# 549-anamdev-forceSensor.net
KiCad netlist of a schematic drawn in EAGLE
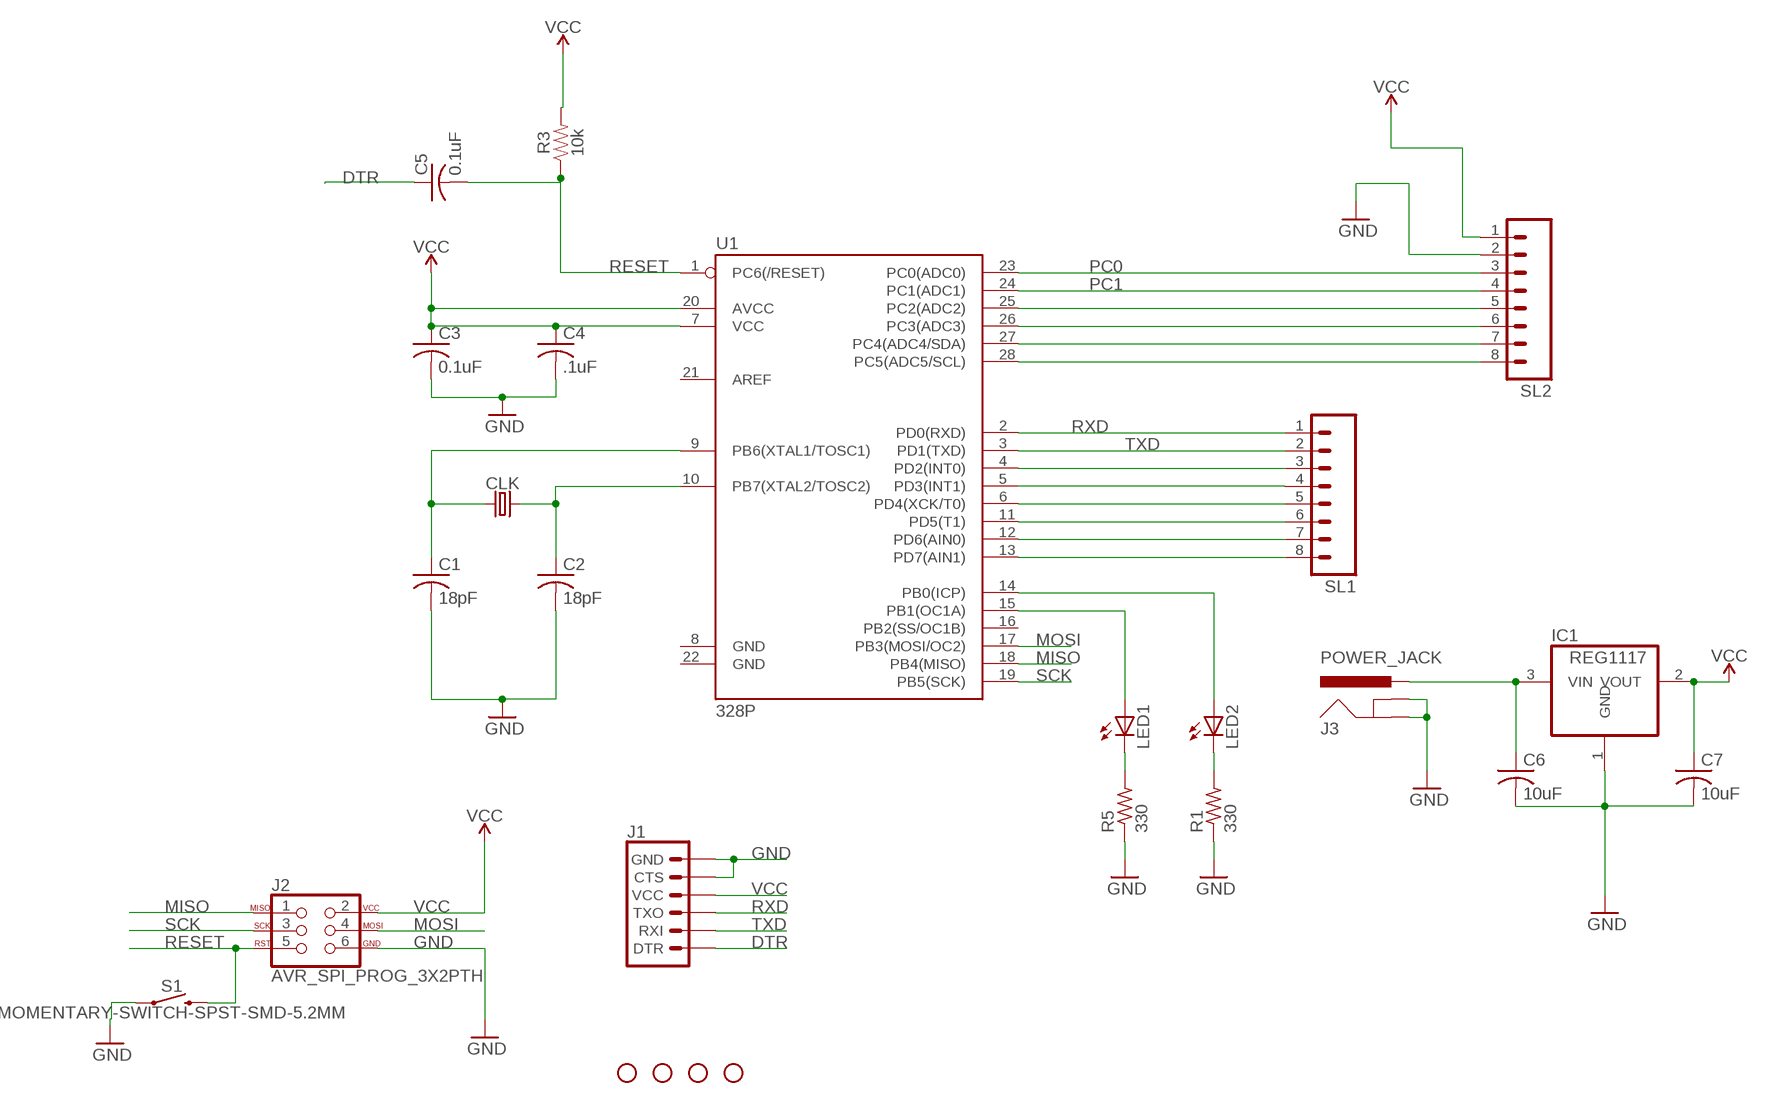
[diagram p0: schematic, sheet 1]
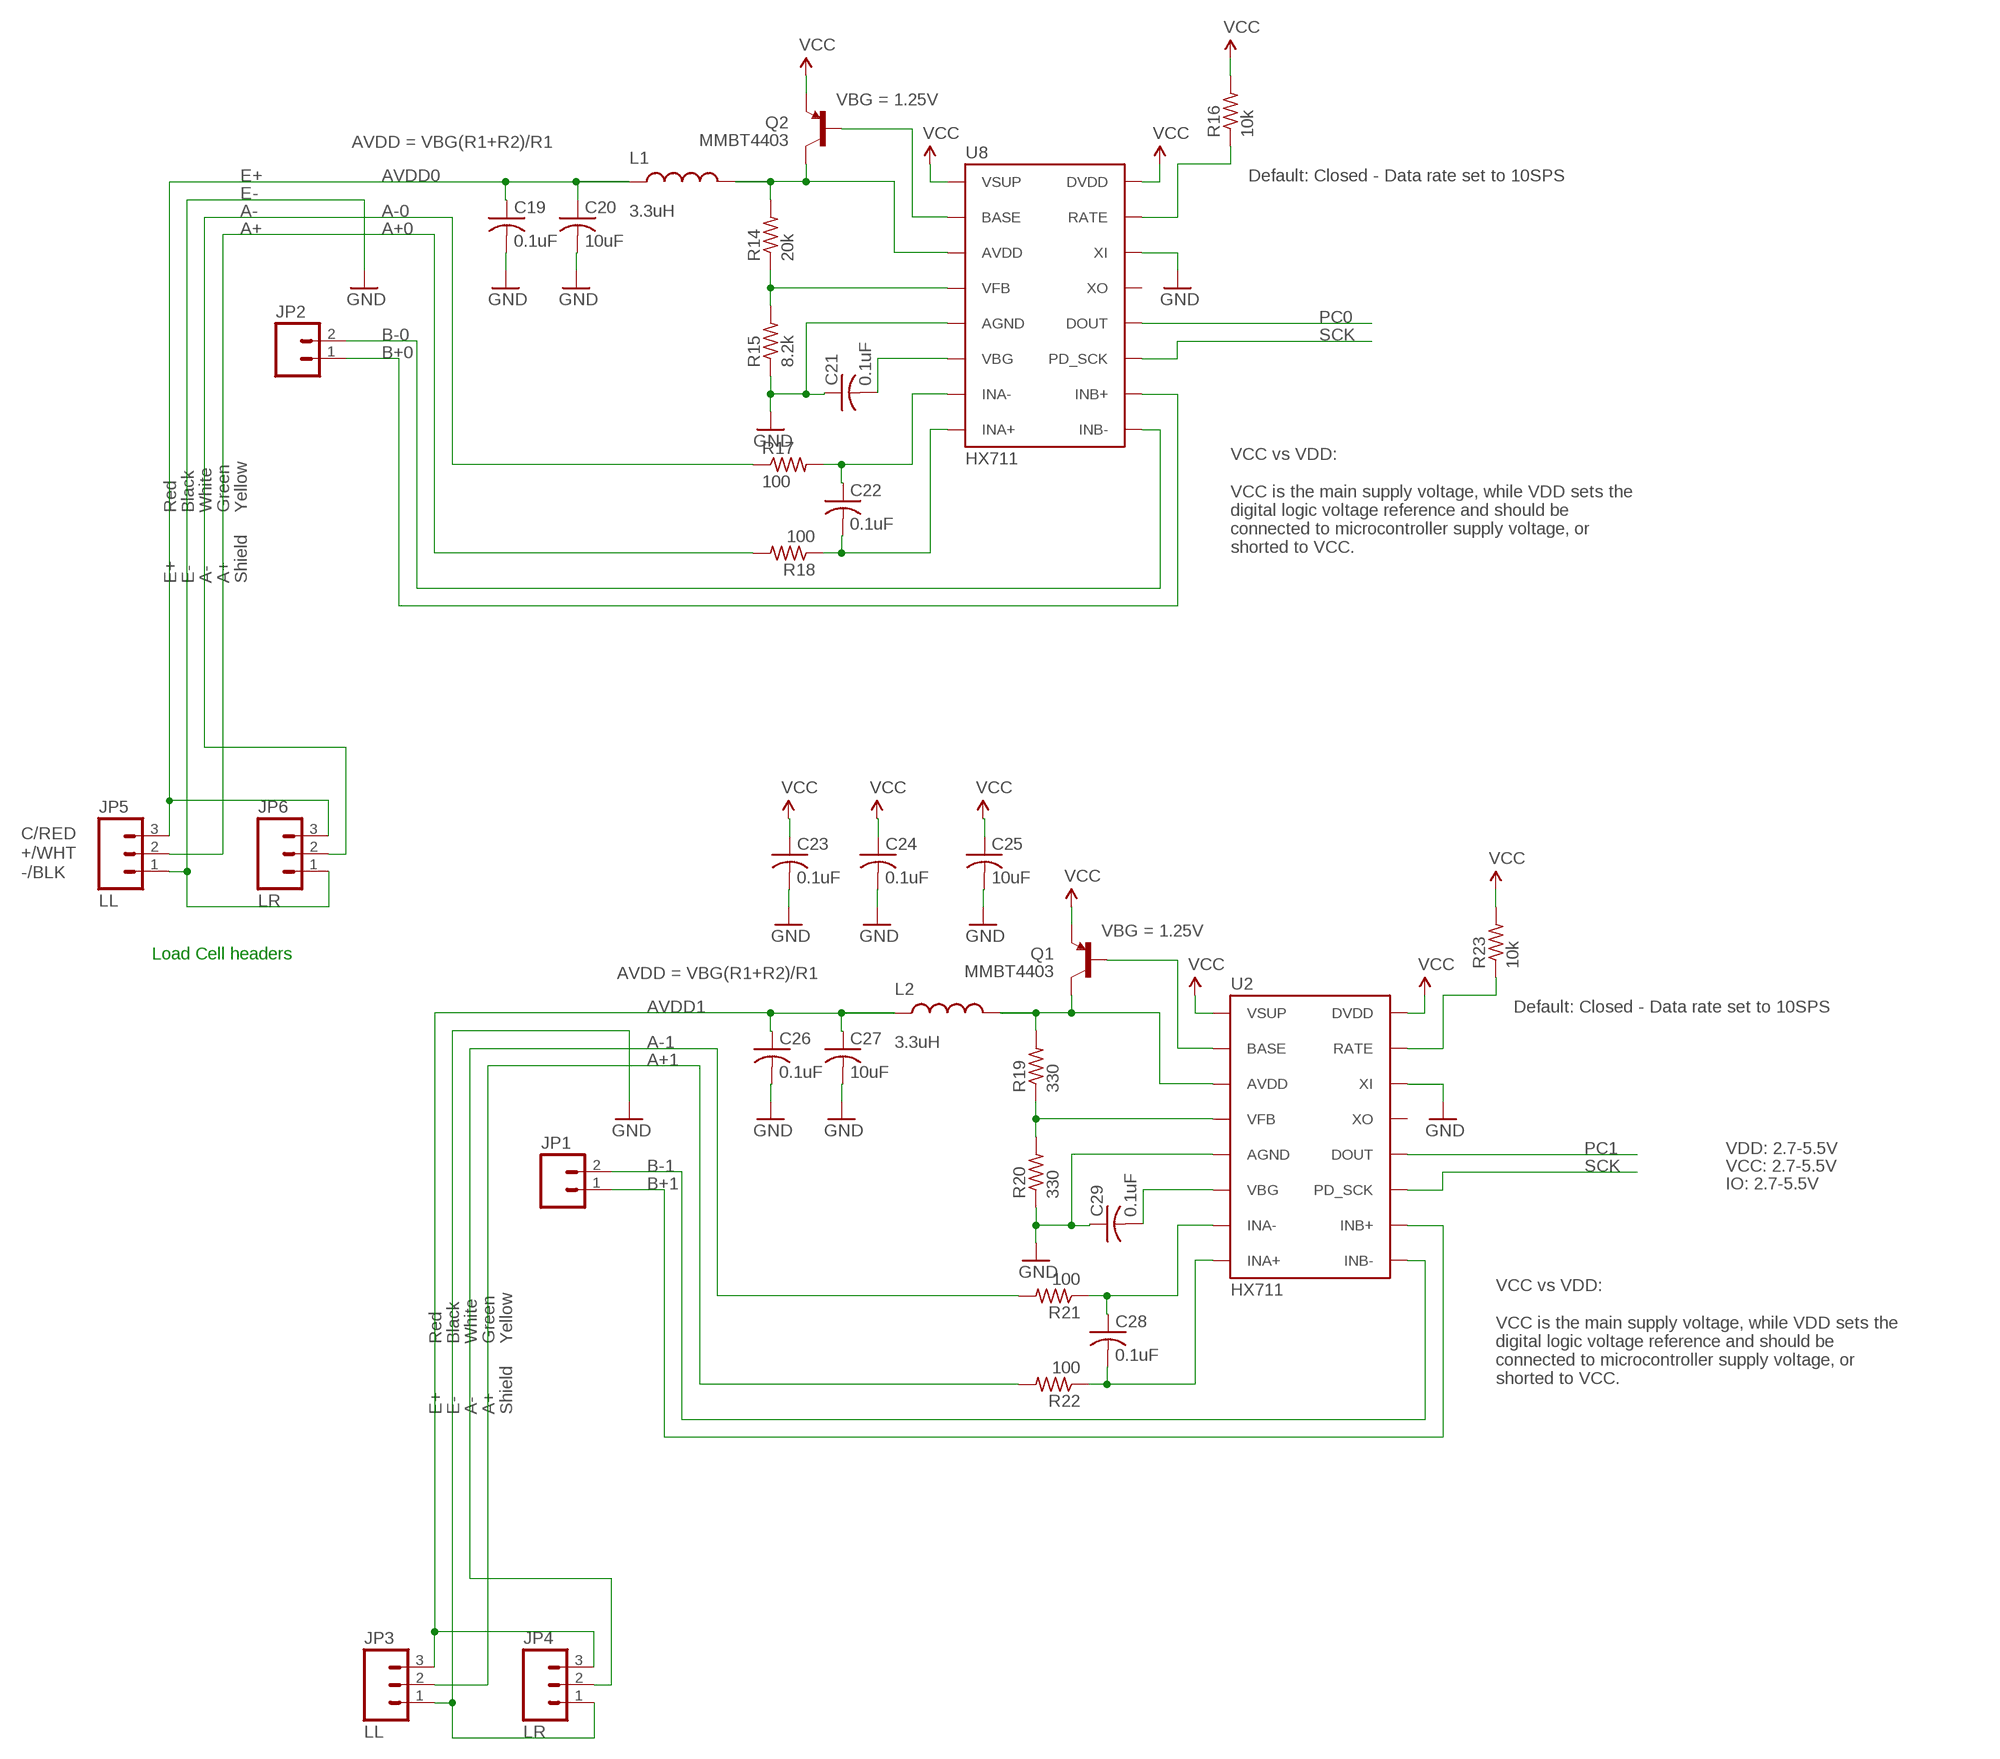
[diagram p1: schematic, sheet 2]

(export (version "E")
  (design (tool "Eeschema 10.0.6"))
  (components
    (comp (ref "C1")
      (value "18pF")
      (footprint "eagle-import:C1206")
      (libsource (lib "eagle-import") (part "C-USC1206"))
    )
    (comp (ref "C2")
      (value "18pF")
      (footprint "eagle-import:C1206")
      (libsource (lib "eagle-import") (part "C-USC1206"))
    )
    (comp (ref "C3")
      (value "0.1uF")
      (footprint "eagle-import:C1206")
      (libsource (lib "eagle-import") (part "C-USC1206"))
    )
    (comp (ref "C4")
      (value ".1uF")
      (footprint "eagle-import:C1206")
      (libsource (lib "eagle-import") (part "C-USC1206"))
    )
    (comp (ref "C5")
      (value "0.1uF")
      (footprint "eagle-import:C1206")
      (libsource (lib "eagle-import") (part "C-USC1206"))
    )
    (comp (ref "C6")
      (value "10uF")
      (footprint "eagle-import:C1206")
      (libsource (lib "eagle-import") (part "C-USC1206"))
    )
    (comp (ref "C7")
      (value "10uF")
      (footprint "eagle-import:C1206")
      (libsource (lib "eagle-import") (part "C-USC1206"))
    )
    (comp (ref "CLK")
      (value "CRYSTALSMD-HC49UP")
      (footprint "eagle-import:HC49UP")
      (libsource (lib "eagle-import") (part "CRYSTALSMD-HC49UP"))
    )
    (comp (ref "H1")
      (value "STAND-OFF")
      (footprint "eagle-import:STAND-OFF")
      (libsource (lib "eagle-import") (part "STAND-OFF"))
    )
    (comp (ref "H2")
      (value "STAND-OFF")
      (footprint "eagle-import:STAND-OFF")
      (libsource (lib "eagle-import") (part "STAND-OFF"))
    )
    (comp (ref "H3")
      (value "STAND-OFF")
      (footprint "eagle-import:STAND-OFF")
      (libsource (lib "eagle-import") (part "STAND-OFF"))
    )
    (comp (ref "H4")
      (value "STAND-OFF")
      (footprint "eagle-import:STAND-OFF")
      (libsource (lib "eagle-import") (part "STAND-OFF"))
    )
    (comp (ref "IC1")
      (value "REG1117")
      (footprint "eagle-import:SOT223")
      (libsource (lib "eagle-import") (part "REG1117"))
    )
    (comp (ref "J1")
      (value "6_PIN_SERIAL_TARGET")
      (footprint "eagle-import:1X06")
      (libsource (lib "eagle-import") (part "6_PIN_SERIAL_TARGET"))
    )
    (comp (ref "J2")
      (value "AVR_SPI_PROG_3X2PTH")
      (footprint "eagle-import:2X3")
      (libsource (lib "eagle-import") (part "AVR_SPI_PROG_3X2PTH"))
    )
    (comp (ref "J3")
      (value "POWER_JACK")
      (footprint "eagle-import:POWER_JACK_PTH")
      (libsource (lib "eagle-import") (part "POWER_JACK"))
    )
    (comp (ref "LED1")
      (value "LED1206")
      (footprint "eagle-import:LED-1206")
      (libsource (lib "eagle-import") (part "LED1206"))
    )
    (comp (ref "LED2")
      (value "LED1206")
      (footprint "eagle-import:LED-1206")
      (libsource (lib "eagle-import") (part "LED1206"))
    )
    (comp (ref "R1")
      (value "330")
      (footprint "eagle-import:R1206")
      (libsource (lib "eagle-import") (part "R-US_R1206"))
    )
    (comp (ref "R3")
      (value "10k")
      (footprint "eagle-import:1206")
      (libsource (lib "eagle-import") (part "10OHM-1206-1/4W-1%"))
    )
    (comp (ref "R5")
      (value "330")
      (footprint "eagle-import:R1206")
      (libsource (lib "eagle-import") (part "R-US_R1206"))
    )
    (comp (ref "S1")
      (value "MOMENTARY-SWITCH-SPST-SMD-5.2MM")
      (footprint "eagle-import:TACTILE_SWITCH_SMD_5.2MM")
      (libsource (lib "eagle-import") (part "MOMENTARY-SWITCH-SPST-SMD-5.2MM"))
    )
    (comp (ref "SL1")
      (value "M08")
      (footprint "eagle-import:08P")
      (libsource (lib "eagle-import") (part "M08"))
    )
    (comp (ref "SL2")
      (value "M08")
      (footprint "eagle-import:08P")
      (libsource (lib "eagle-import") (part "M08"))
    )
    (comp (ref "U1")
      (value "328P")
      (footprint "eagle-import:DIP28")
      (libsource (lib "eagle-import") (part "ATMEGA328P_PDIP"))
    )
    (comp (ref "C19")
      (value "0.1uF")
      (footprint "eagle-import:C1206")
      (libsource (lib "eagle-import") (part "C-USC1206"))
    )
    (comp (ref "C20")
      (value "10uF")
      (footprint "eagle-import:C1206")
      (libsource (lib "eagle-import") (part "C-USC1206"))
    )
    (comp (ref "C21")
      (value "0.1uF")
      (footprint "eagle-import:C1206")
      (libsource (lib "eagle-import") (part "C-USC1206"))
    )
    (comp (ref "C22")
      (value "0.1uF")
      (footprint "eagle-import:C1206")
      (libsource (lib "eagle-import") (part "C-USC1206"))
    )
    (comp (ref "C23")
      (value "0.1uF")
      (footprint "eagle-import:C1206")
      (libsource (lib "eagle-import") (part "C-USC1206"))
    )
    (comp (ref "C24")
      (value "0.1uF")
      (footprint "eagle-import:C1206")
      (libsource (lib "eagle-import") (part "C-USC1206"))
    )
    (comp (ref "C25")
      (value "10uF")
      (footprint "eagle-import:C1206")
      (libsource (lib "eagle-import") (part "C-USC1206"))
    )
    (comp (ref "C26")
      (value "0.1uF")
      (footprint "eagle-import:C1206")
      (libsource (lib "eagle-import") (part "C-USC1206"))
    )
    (comp (ref "C27")
      (value "10uF")
      (footprint "eagle-import:C1206")
      (libsource (lib "eagle-import") (part "C-USC1206"))
    )
    (comp (ref "C28")
      (value "0.1uF")
      (footprint "eagle-import:C1206")
      (libsource (lib "eagle-import") (part "C-USC1206"))
    )
    (comp (ref "C29")
      (value "0.1uF")
      (footprint "eagle-import:C1206")
      (libsource (lib "eagle-import") (part "C-USC1206"))
    )
    (comp (ref "JP1")
      (value "M02PTH")
      (footprint "eagle-import:1X02")
      (libsource (lib "eagle-import") (part "M02PTH"))
    )
    (comp (ref "JP2")
      (value "M02PTH")
      (footprint "eagle-import:1X02")
      (libsource (lib "eagle-import") (part "M02PTH"))
    )
    (comp (ref "JP3")
      (value "LL")
      (footprint "eagle-import:1X03")
      (libsource (lib "eagle-import") (part "M03PTH"))
    )
    (comp (ref "JP4")
      (value "LR")
      (footprint "eagle-import:1X03")
      (libsource (lib "eagle-import") (part "M03PTH"))
    )
    (comp (ref "JP5")
      (value "LL")
      (footprint "eagle-import:1X03")
      (libsource (lib "eagle-import") (part "M03PTH"))
    )
    (comp (ref "JP6")
      (value "LR")
      (footprint "eagle-import:1X03")
      (libsource (lib "eagle-import") (part "M03PTH"))
    )
    (comp (ref "L1")
      (value "3.3uH")
      (footprint "eagle-import:0805")
      (libsource (lib "eagle-import") (part "INDUCTOR0805-IND"))
    )
    (comp (ref "L2")
      (value "3.3uH")
      (footprint "eagle-import:0805")
      (libsource (lib "eagle-import") (part "INDUCTOR0805-IND"))
    )
    (comp (ref "Q1")
      (value "MMBT4403")
      (footprint "eagle-import:SOT23-3")
      (libsource (lib "eagle-import") (part "TRANSISTOR_PNPMMBT4403"))
    )
    (comp (ref "Q2")
      (value "MMBT4403")
      (footprint "eagle-import:SOT23-3")
      (libsource (lib "eagle-import") (part "TRANSISTOR_PNPMMBT4403"))
    )
    (comp (ref "R14")
      (value "20k")
      (footprint "eagle-import:R1206")
      (libsource (lib "eagle-import") (part "R-US_R1206"))
    )
    (comp (ref "R15")
      (value "8.2k")
      (footprint "eagle-import:R1206")
      (libsource (lib "eagle-import") (part "R-US_R1206"))
    )
    (comp (ref "R16")
      (value "10k")
      (footprint "eagle-import:R1206")
      (libsource (lib "eagle-import") (part "R-US_R1206"))
    )
    (comp (ref "R17")
      (value "100")
      (footprint "eagle-import:R1206")
      (libsource (lib "eagle-import") (part "R-US_R1206"))
    )
    (comp (ref "R18")
      (value "100")
      (footprint "eagle-import:R1206")
      (libsource (lib "eagle-import") (part "R-US_R1206"))
    )
    (comp (ref "R19")
      (value "330")
      (footprint "eagle-import:R1206")
      (libsource (lib "eagle-import") (part "R-US_R1206"))
    )
    (comp (ref "R20")
      (value "330")
      (footprint "eagle-import:R1206")
      (libsource (lib "eagle-import") (part "R-US_R1206"))
    )
    (comp (ref "R21")
      (value "100")
      (footprint "eagle-import:R1206")
      (libsource (lib "eagle-import") (part "R-US_R1206"))
    )
    (comp (ref "R22")
      (value "100")
      (footprint "eagle-import:R1206")
      (libsource (lib "eagle-import") (part "R-US_R1206"))
    )
    (comp (ref "R23")
      (value "10k")
      (footprint "eagle-import:R1206")
      (libsource (lib "eagle-import") (part "R-US_R1206"))
    )
    (comp (ref "U2")
      (value "HX711")
      (footprint "eagle-import:SO16")
      (libsource (lib "eagle-import") (part "HX711HX711"))
    )
    (comp (ref "U8")
      (value "HX711")
      (footprint "eagle-import:SO16")
      (libsource (lib "eagle-import") (part "HX711HX711"))
    )
  )
  (nets
    (net (code "1") (name "A+0") (class "Default")
      (node (ref "JP5") (pin "2") (pinfunction "2_2") (pintype "passive"))
      (node (ref "R18") (pin "2") (pinfunction "2_2") (pintype "passive"))
    )
    (net (code "2") (name "A+1") (class "Default")
      (node (ref "JP3") (pin "2") (pinfunction "2_2") (pintype "passive"))
      (node (ref "R22") (pin "2") (pinfunction "2_2") (pintype "passive"))
    )
    (net (code "3") (name "A-0") (class "Default")
      (node (ref "JP6") (pin "2") (pinfunction "2_2") (pintype "passive"))
      (node (ref "R17") (pin "1") (pinfunction "1_1") (pintype "passive"))
    )
    (net (code "4") (name "A-1") (class "Default")
      (node (ref "JP4") (pin "2") (pinfunction "2_2") (pintype "passive"))
      (node (ref "R21") (pin "2") (pinfunction "2_2") (pintype "passive"))
    )
    (net (code "5") (name "AVDD0") (class "Default")
      (node (ref "C19") (pin "1") (pinfunction "1_1") (pintype "passive"))
      (node (ref "C20") (pin "1") (pinfunction "1_1") (pintype "passive"))
      (node (ref "JP5") (pin "3") (pinfunction "3_3") (pintype "passive"))
      (node (ref "JP6") (pin "3") (pinfunction "3_3") (pintype "passive"))
      (node (ref "L1") (pin "1") (pinfunction "1_1") (pintype "passive"))
    )
    (net (code "6") (name "AVDD1") (class "Default")
      (node (ref "C26") (pin "1") (pinfunction "1_1") (pintype "passive"))
      (node (ref "C27") (pin "1") (pinfunction "1_1") (pintype "passive"))
      (node (ref "JP3") (pin "3") (pinfunction "3_3") (pintype "passive"))
      (node (ref "JP4") (pin "3") (pinfunction "3_3") (pintype "passive"))
      (node (ref "L2") (pin "1") (pinfunction "1_1") (pintype "passive"))
    )
    (net (code "7") (name "B+0") (class "Default")
      (node (ref "JP2") (pin "1") (pinfunction "1_1") (pintype "passive"))
      (node (ref "U8") (pin "10") (pinfunction "INB+_10") (pintype "bidirectional"))
    )
    (net (code "8") (name "B+1") (class "Default")
      (node (ref "JP1") (pin "1") (pinfunction "1_1") (pintype "passive"))
      (node (ref "U2") (pin "10") (pinfunction "INB+_10") (pintype "bidirectional"))
    )
    (net (code "9") (name "B-0") (class "Default")
      (node (ref "JP2") (pin "2") (pinfunction "2_2") (pintype "passive"))
      (node (ref "U8") (pin "9") (pinfunction "INB-_9") (pintype "bidirectional"))
    )
    (net (code "10") (name "B-1") (class "Default")
      (node (ref "JP1") (pin "2") (pinfunction "2_2") (pintype "passive"))
      (node (ref "U2") (pin "9") (pinfunction "INB-_9") (pintype "bidirectional"))
    )
    (net (code "11") (name "DTR") (class "Default")
      (node (ref "C5") (pin "1") (pinfunction "1_1") (pintype "passive"))
      (node (ref "J1") (pin "1") (pinfunction "DTR_1") (pintype "passive"))
    )
    (net (code "12") (name "GND") (class "Default")
      (node (ref "C1") (pin "2") (pinfunction "2_2") (pintype "passive"))
      (node (ref "C19") (pin "2") (pinfunction "2_2") (pintype "passive"))
      (node (ref "C2") (pin "2") (pinfunction "2_2") (pintype "passive"))
      (node (ref "C20") (pin "2") (pinfunction "2_2") (pintype "passive"))
      (node (ref "C21") (pin "1") (pinfunction "1_1") (pintype "passive"))
      (node (ref "C23") (pin "2") (pinfunction "2_2") (pintype "passive"))
      (node (ref "C24") (pin "2") (pinfunction "2_2") (pintype "passive"))
      (node (ref "C25") (pin "2") (pinfunction "2_2") (pintype "passive"))
      (node (ref "C26") (pin "2") (pinfunction "2_2") (pintype "passive"))
      (node (ref "C27") (pin "2") (pinfunction "2_2") (pintype "passive"))
      (node (ref "C29") (pin "1") (pinfunction "1_1") (pintype "passive"))
      (node (ref "C3") (pin "2") (pinfunction "2_2") (pintype "passive"))
      (node (ref "C4") (pin "2") (pinfunction "2_2") (pintype "passive"))
      (node (ref "C6") (pin "2") (pinfunction "2_2") (pintype "passive"))
      (node (ref "C7") (pin "2") (pinfunction "2_2") (pintype "passive"))
      (node (ref "IC1") (pin "1") (pinfunction "GND_1") (pintype "power_in"))
      (node (ref "J1") (pin "5") (pinfunction "CTS_5") (pintype "passive"))
      (node (ref "J1") (pin "6") (pinfunction "GND_6") (pintype "passive"))
      (node (ref "J2") (pin "6") (pinfunction "6_6") (pintype "passive"))
      (node (ref "J3") (pin "GND") (pinfunction "GND_GND") (pintype "bidirectional"))
      (node (ref "J3") (pin "GNDBREAK") (pinfunction "GNDBREAK_GNDBREAK") (pintype "bidirectional"))
      (node (ref "JP3") (pin "1") (pinfunction "1_1") (pintype "passive"))
      (node (ref "JP4") (pin "1") (pinfunction "1_1") (pintype "passive"))
      (node (ref "JP5") (pin "1") (pinfunction "1_1") (pintype "passive"))
      (node (ref "JP6") (pin "1") (pinfunction "1_1") (pintype "passive"))
      (node (ref "R1") (pin "1") (pinfunction "1_1") (pintype "passive"))
      (node (ref "R15") (pin "1") (pinfunction "1_1") (pintype "passive"))
      (node (ref "R20") (pin "1") (pinfunction "1_1") (pintype "passive"))
      (node (ref "R5") (pin "1") (pinfunction "1_1") (pintype "passive"))
      (node (ref "S1") (pin "1") (pinfunction "1_1") (pintype "passive"))
      (node (ref "SL2") (pin "2") (pinfunction "2_2") (pintype "passive"))
      (node (ref "U2") (pin "14") (pinfunction "XI_14") (pintype "bidirectional"))
      (node (ref "U2") (pin "5") (pinfunction "AGND_5") (pintype "bidirectional"))
      (node (ref "U8") (pin "14") (pinfunction "XI_14") (pintype "bidirectional"))
      (node (ref "U8") (pin "5") (pinfunction "AGND_5") (pintype "bidirectional"))
    )
    (net (code "13") (name "MISO") (class "Default")
      (node (ref "J2") (pin "1") (pinfunction "1_1") (pintype "passive"))
      (node (ref "U1") (pin "18") (pinfunction "PB4(MISO)_18") (pintype "bidirectional"))
    )
    (net (code "14") (name "MOSI") (class "Default")
      (node (ref "J2") (pin "4") (pinfunction "4_4") (pintype "passive"))
      (node (ref "U1") (pin "17") (pinfunction "PB3(MOSI/OC2)_17") (pintype "bidirectional"))
    )
    (net (code "15") (name "Net-(IC1-VIN)") (class "Default")
      (node (ref "C6") (pin "1") (pinfunction "1_1") (pintype "passive"))
      (node (ref "IC1") (pin "3") (pinfunction "VIN_3") (pintype "input"))
      (node (ref "J3") (pin "PWR") (pinfunction "PWR_PWR") (pintype "bidirectional"))
    )
    (net (code "16") (name "Net-(LED1-PadC)") (class "Default")
      (node (ref "LED1") (pin "C") (pinfunction "C_C") (pintype "passive"))
      (node (ref "R5") (pin "2") (pinfunction "2_2") (pintype "passive"))
    )
    (net (code "17") (name "Net-(LED2-PadC)") (class "Default")
      (node (ref "LED2") (pin "C") (pinfunction "C_C") (pintype "passive"))
      (node (ref "R1") (pin "2") (pinfunction "2_2") (pintype "passive"))
    )
    (net (code "18") (name "Net-(Q1-B)") (class "Default")
      (node (ref "Q1") (pin "1") (pinfunction "B_1") (pintype "passive"))
      (node (ref "U2") (pin "2") (pinfunction "BASE_2") (pintype "bidirectional"))
    )
    (net (code "19") (name "Net-(Q1-C)") (class "Default")
      (node (ref "L2") (pin "2") (pinfunction "2_2") (pintype "passive"))
      (node (ref "Q1") (pin "3") (pinfunction "C_3") (pintype "passive"))
      (node (ref "R19") (pin "2") (pinfunction "2_2") (pintype "passive"))
      (node (ref "U2") (pin "3") (pinfunction "AVDD_3") (pintype "bidirectional"))
    )
    (net (code "20") (name "Net-(Q2-B)") (class "Default")
      (node (ref "Q2") (pin "1") (pinfunction "B_1") (pintype "passive"))
      (node (ref "U8") (pin "2") (pinfunction "BASE_2") (pintype "bidirectional"))
    )
    (net (code "21") (name "Net-(Q2-C)") (class "Default")
      (node (ref "L1") (pin "2") (pinfunction "2_2") (pintype "passive"))
      (node (ref "Q2") (pin "3") (pinfunction "C_3") (pintype "passive"))
      (node (ref "R14") (pin "2") (pinfunction "2_2") (pintype "passive"))
      (node (ref "U8") (pin "3") (pinfunction "AVDD_3") (pintype "bidirectional"))
    )
    (net (code "22") (name "Net-(U1-PB0(ICP))") (class "Default")
      (node (ref "LED2") (pin "A") (pinfunction "A_A") (pintype "passive"))
      (node (ref "U1") (pin "14") (pinfunction "PB0(ICP)_14") (pintype "bidirectional"))
    )
    (net (code "23") (name "Net-(U1-PB1(OC1A))") (class "Default")
      (node (ref "LED1") (pin "A") (pinfunction "A_A") (pintype "passive"))
      (node (ref "U1") (pin "15") (pinfunction "PB1(OC1A)_15") (pintype "bidirectional"))
    )
    (net (code "24") (name "Net-(U1-PB6(XTAL1{slash}TOSC1))") (class "Default")
      (node (ref "C1") (pin "1") (pinfunction "1_1") (pintype "passive"))
      (node (ref "CLK") (pin "1") (pinfunction "1_1") (pintype "passive"))
      (node (ref "U1") (pin "9") (pinfunction "PB6(XTAL1/TOSC1)_9") (pintype "bidirectional"))
    )
    (net (code "25") (name "Net-(U1-PB7(XTAL2{slash}TOSC2))") (class "Default")
      (node (ref "C2") (pin "1") (pinfunction "1_1") (pintype "passive"))
      (node (ref "CLK") (pin "2") (pinfunction "2_2") (pintype "passive"))
      (node (ref "U1") (pin "10") (pinfunction "PB7(XTAL2/TOSC2)_10") (pintype "bidirectional"))
    )
    (net (code "26") (name "Net-(U1-PC2(ADC2))") (class "Default")
      (node (ref "SL2") (pin "5") (pinfunction "5_5") (pintype "passive"))
      (node (ref "U1") (pin "25") (pinfunction "PC2(ADC2)_25") (pintype "bidirectional"))
    )
    (net (code "27") (name "Net-(U1-PC3(ADC3))") (class "Default")
      (node (ref "SL2") (pin "6") (pinfunction "6_6") (pintype "passive"))
      (node (ref "U1") (pin "26") (pinfunction "PC3(ADC3)_26") (pintype "bidirectional"))
    )
    (net (code "28") (name "Net-(U1-PC4(ADC4{slash}SDA))") (class "Default")
      (node (ref "SL2") (pin "7") (pinfunction "7_7") (pintype "passive"))
      (node (ref "U1") (pin "27") (pinfunction "PC4(ADC4/SDA)_27") (pintype "bidirectional"))
    )
    (net (code "29") (name "Net-(U1-PC5(ADC5{slash}SCL))") (class "Default")
      (node (ref "SL2") (pin "8") (pinfunction "8_8") (pintype "passive"))
      (node (ref "U1") (pin "28") (pinfunction "PC5(ADC5/SCL)_28") (pintype "bidirectional"))
    )
    (net (code "30") (name "Net-(U1-PD2(INT0))") (class "Default")
      (node (ref "SL1") (pin "3") (pinfunction "3_3") (pintype "passive"))
      (node (ref "U1") (pin "4") (pinfunction "PD2(INT0)_4") (pintype "bidirectional"))
    )
    (net (code "31") (name "Net-(U1-PD3(INT1))") (class "Default")
      (node (ref "SL1") (pin "4") (pinfunction "4_4") (pintype "passive"))
      (node (ref "U1") (pin "5") (pinfunction "PD3(INT1)_5") (pintype "bidirectional"))
    )
    (net (code "32") (name "Net-(U1-PD4(XCK{slash}T0))") (class "Default")
      (node (ref "SL1") (pin "5") (pinfunction "5_5") (pintype "passive"))
      (node (ref "U1") (pin "6") (pinfunction "PD4(XCK/T0)_6") (pintype "bidirectional"))
    )
    (net (code "33") (name "Net-(U1-PD5(T1))") (class "Default")
      (node (ref "SL1") (pin "6") (pinfunction "6_6") (pintype "passive"))
      (node (ref "U1") (pin "11") (pinfunction "PD5(T1)_11") (pintype "bidirectional"))
    )
    (net (code "34") (name "Net-(U1-PD6(AIN0))") (class "Default")
      (node (ref "SL1") (pin "7") (pinfunction "7_7") (pintype "passive"))
      (node (ref "U1") (pin "12") (pinfunction "PD6(AIN0)_12") (pintype "bidirectional"))
    )
    (net (code "35") (name "Net-(U1-PD7(AIN1))") (class "Default")
      (node (ref "SL1") (pin "8") (pinfunction "8_8") (pintype "passive"))
      (node (ref "U1") (pin "13") (pinfunction "PD7(AIN1)_13") (pintype "bidirectional"))
    )
    (net (code "36") (name "Net-(U2-INA+)") (class "Default")
      (node (ref "C28") (pin "2") (pinfunction "2_2") (pintype "passive"))
      (node (ref "R22") (pin "1") (pinfunction "1_1") (pintype "passive"))
      (node (ref "U2") (pin "8") (pinfunction "INA+_8") (pintype "bidirectional"))
    )
    (net (code "37") (name "Net-(U2-INA-)") (class "Default")
      (node (ref "C28") (pin "1") (pinfunction "1_1") (pintype "passive"))
      (node (ref "R21") (pin "1") (pinfunction "1_1") (pintype "passive"))
      (node (ref "U2") (pin "7") (pinfunction "INA-_7") (pintype "bidirectional"))
    )
    (net (code "38") (name "Net-(U2-RATE)") (class "Default")
      (node (ref "R23") (pin "1") (pinfunction "1_1") (pintype "passive"))
      (node (ref "U2") (pin "15") (pinfunction "RATE_15") (pintype "bidirectional"))
    )
    (net (code "39") (name "Net-(U2-VBG)") (class "Default")
      (node (ref "C29") (pin "2") (pinfunction "2_2") (pintype "passive"))
      (node (ref "U2") (pin "6") (pinfunction "VBG_6") (pintype "bidirectional"))
    )
    (net (code "40") (name "Net-(U2-VFB)") (class "Default")
      (node (ref "R19") (pin "1") (pinfunction "1_1") (pintype "passive"))
      (node (ref "R20") (pin "2") (pinfunction "2_2") (pintype "passive"))
      (node (ref "U2") (pin "4") (pinfunction "VFB_4") (pintype "bidirectional"))
    )
    (net (code "41") (name "Net-(U8-INA+)") (class "Default")
      (node (ref "C22") (pin "2") (pinfunction "2_2") (pintype "passive"))
      (node (ref "R18") (pin "1") (pinfunction "1_1") (pintype "passive"))
      (node (ref "U8") (pin "8") (pinfunction "INA+_8") (pintype "bidirectional"))
    )
    (net (code "42") (name "Net-(U8-INA-)") (class "Default")
      (node (ref "C22") (pin "1") (pinfunction "1_1") (pintype "passive"))
      (node (ref "R17") (pin "2") (pinfunction "2_2") (pintype "passive"))
      (node (ref "U8") (pin "7") (pinfunction "INA-_7") (pintype "bidirectional"))
    )
    (net (code "43") (name "Net-(U8-RATE)") (class "Default")
      (node (ref "R16") (pin "1") (pinfunction "1_1") (pintype "passive"))
      (node (ref "U8") (pin "15") (pinfunction "RATE_15") (pintype "bidirectional"))
    )
    (net (code "44") (name "Net-(U8-VBG)") (class "Default")
      (node (ref "C21") (pin "2") (pinfunction "2_2") (pintype "passive"))
      (node (ref "U8") (pin "6") (pinfunction "VBG_6") (pintype "bidirectional"))
    )
    (net (code "45") (name "Net-(U8-VFB)") (class "Default")
      (node (ref "R14") (pin "1") (pinfunction "1_1") (pintype "passive"))
      (node (ref "R15") (pin "2") (pinfunction "2_2") (pintype "passive"))
      (node (ref "U8") (pin "4") (pinfunction "VFB_4") (pintype "bidirectional"))
    )
    (net (code "46") (name "PC0") (class "Default")
      (node (ref "SL2") (pin "3") (pinfunction "3_3") (pintype "passive"))
      (node (ref "U1") (pin "23") (pinfunction "PC0(ADC0)_23") (pintype "bidirectional"))
      (node (ref "U8") (pin "12") (pinfunction "DOUT_12") (pintype "bidirectional"))
    )
    (net (code "47") (name "PC1") (class "Default")
      (node (ref "SL2") (pin "4") (pinfunction "4_4") (pintype "passive"))
      (node (ref "U1") (pin "24") (pinfunction "PC1(ADC1)_24") (pintype "bidirectional"))
      (node (ref "U2") (pin "12") (pinfunction "DOUT_12") (pintype "bidirectional"))
    )
    (net (code "48") (name "RESET") (class "Default")
      (node (ref "C5") (pin "2") (pinfunction "2_2") (pintype "passive"))
      (node (ref "J2") (pin "5") (pinfunction "5_5") (pintype "passive"))
      (node (ref "R3") (pin "1") (pinfunction "1_1") (pintype "passive"))
      (node (ref "S1") (pin "3") (pinfunction "2_3") (pintype "passive"))
      (node (ref "U1") (pin "1") (pinfunction "PC6(/RESET)_1") (pintype "bidirectional"))
    )
    (net (code "49") (name "RXD") (class "Default")
      (node (ref "J1") (pin "3") (pinfunction "TXO_3") (pintype "passive"))
      (node (ref "SL1") (pin "1") (pinfunction "1_1") (pintype "passive"))
      (node (ref "U1") (pin "2") (pinfunction "PD0(RXD)_2") (pintype "bidirectional"))
    )
    (net (code "50") (name "SCK") (class "Default")
      (node (ref "J2") (pin "3") (pinfunction "3_3") (pintype "passive"))
      (node (ref "U1") (pin "19") (pinfunction "PB5(SCK)_19") (pintype "bidirectional"))
      (node (ref "U2") (pin "11") (pinfunction "PD_SCK_11") (pintype "bidirectional"))
      (node (ref "U8") (pin "11") (pinfunction "PD_SCK_11") (pintype "bidirectional"))
    )
    (net (code "51") (name "TXD") (class "Default")
      (node (ref "J1") (pin "2") (pinfunction "RXI_2") (pintype "passive"))
      (node (ref "SL1") (pin "2") (pinfunction "2_2") (pintype "passive"))
      (node (ref "U1") (pin "3") (pinfunction "PD1(TXD)_3") (pintype "bidirectional"))
    )
    (net (code "52") (name "VCC") (class "Default")
      (node (ref "C23") (pin "1") (pinfunction "1_1") (pintype "passive"))
      (node (ref "C24") (pin "1") (pinfunction "1_1") (pintype "passive"))
      (node (ref "C25") (pin "1") (pinfunction "1_1") (pintype "passive"))
      (node (ref "C3") (pin "1") (pinfunction "1_1") (pintype "passive"))
      (node (ref "C4") (pin "1") (pinfunction "1_1") (pintype "passive"))
      (node (ref "C7") (pin "1") (pinfunction "1_1") (pintype "passive"))
      (node (ref "IC1") (pin "2") (pinfunction "VOUT_2") (pintype "output"))
      (node (ref "J1") (pin "4") (pinfunction "VCC_4") (pintype "passive"))
      (node (ref "J2") (pin "2") (pinfunction "2_2") (pintype "passive"))
      (node (ref "Q1") (pin "2") (pinfunction "E_2") (pintype "passive"))
      (node (ref "Q2") (pin "2") (pinfunction "E_2") (pintype "passive"))
      (node (ref "R16") (pin "2") (pinfunction "2_2") (pintype "passive"))
      (node (ref "R23") (pin "2") (pinfunction "2_2") (pintype "passive"))
      (node (ref "R3") (pin "2") (pinfunction "2_2") (pintype "passive"))
      (node (ref "SL2") (pin "1") (pinfunction "1_1") (pintype "passive"))
      (node (ref "U1") (pin "20") (pinfunction "AVCC_20") (pintype "bidirectional"))
      (node (ref "U1") (pin "7") (pinfunction "VCC_7") (pintype "bidirectional"))
      (node (ref "U2") (pin "1") (pinfunction "VSUP_1") (pintype "bidirectional"))
      (node (ref "U2") (pin "16") (pinfunction "DVDD_16") (pintype "bidirectional"))
      (node (ref "U8") (pin "1") (pinfunction "VSUP_1") (pintype "bidirectional"))
      (node (ref "U8") (pin "16") (pinfunction "DVDD_16") (pintype "bidirectional"))
    )
    (net (code "53") (name "unconnected-(U1-AREF-Pad21)") (class "Default")
      (node (ref "U1") (pin "21") (pinfunction "AREF_21") (pintype "bidirectional"))
    )
    (net (code "54") (name "unconnected-(U1-GND-Pad8)") (class "Default")
      (node (ref "U1") (pin "8") (pinfunction "GND_8") (pintype "bidirectional"))
    )
    (net (code "55") (name "unconnected-(U1-GND-Pad22)") (class "Default")
      (node (ref "U1") (pin "22") (pinfunction "GND_22") (pintype "bidirectional"))
    )
    (net (code "56") (name "unconnected-(U1-PB2(SS{slash}OC1B)-Pad16)") (class "Default")
      (node (ref "U1") (pin "16") (pinfunction "PB2(SS/OC1B)_16") (pintype "bidirectional"))
    )
    (net (code "57") (name "unconnected-(U2-XO-Pad13)") (class "Default")
      (node (ref "U2") (pin "13") (pinfunction "XO_13") (pintype "bidirectional"))
    )
    (net (code "58") (name "unconnected-(U8-XO-Pad13)") (class "Default")
      (node (ref "U8") (pin "13") (pinfunction "XO_13") (pintype "bidirectional"))
    )
  )
)
